# Tree.net
KiCad netlist of a schematic drawn in Altium Designer
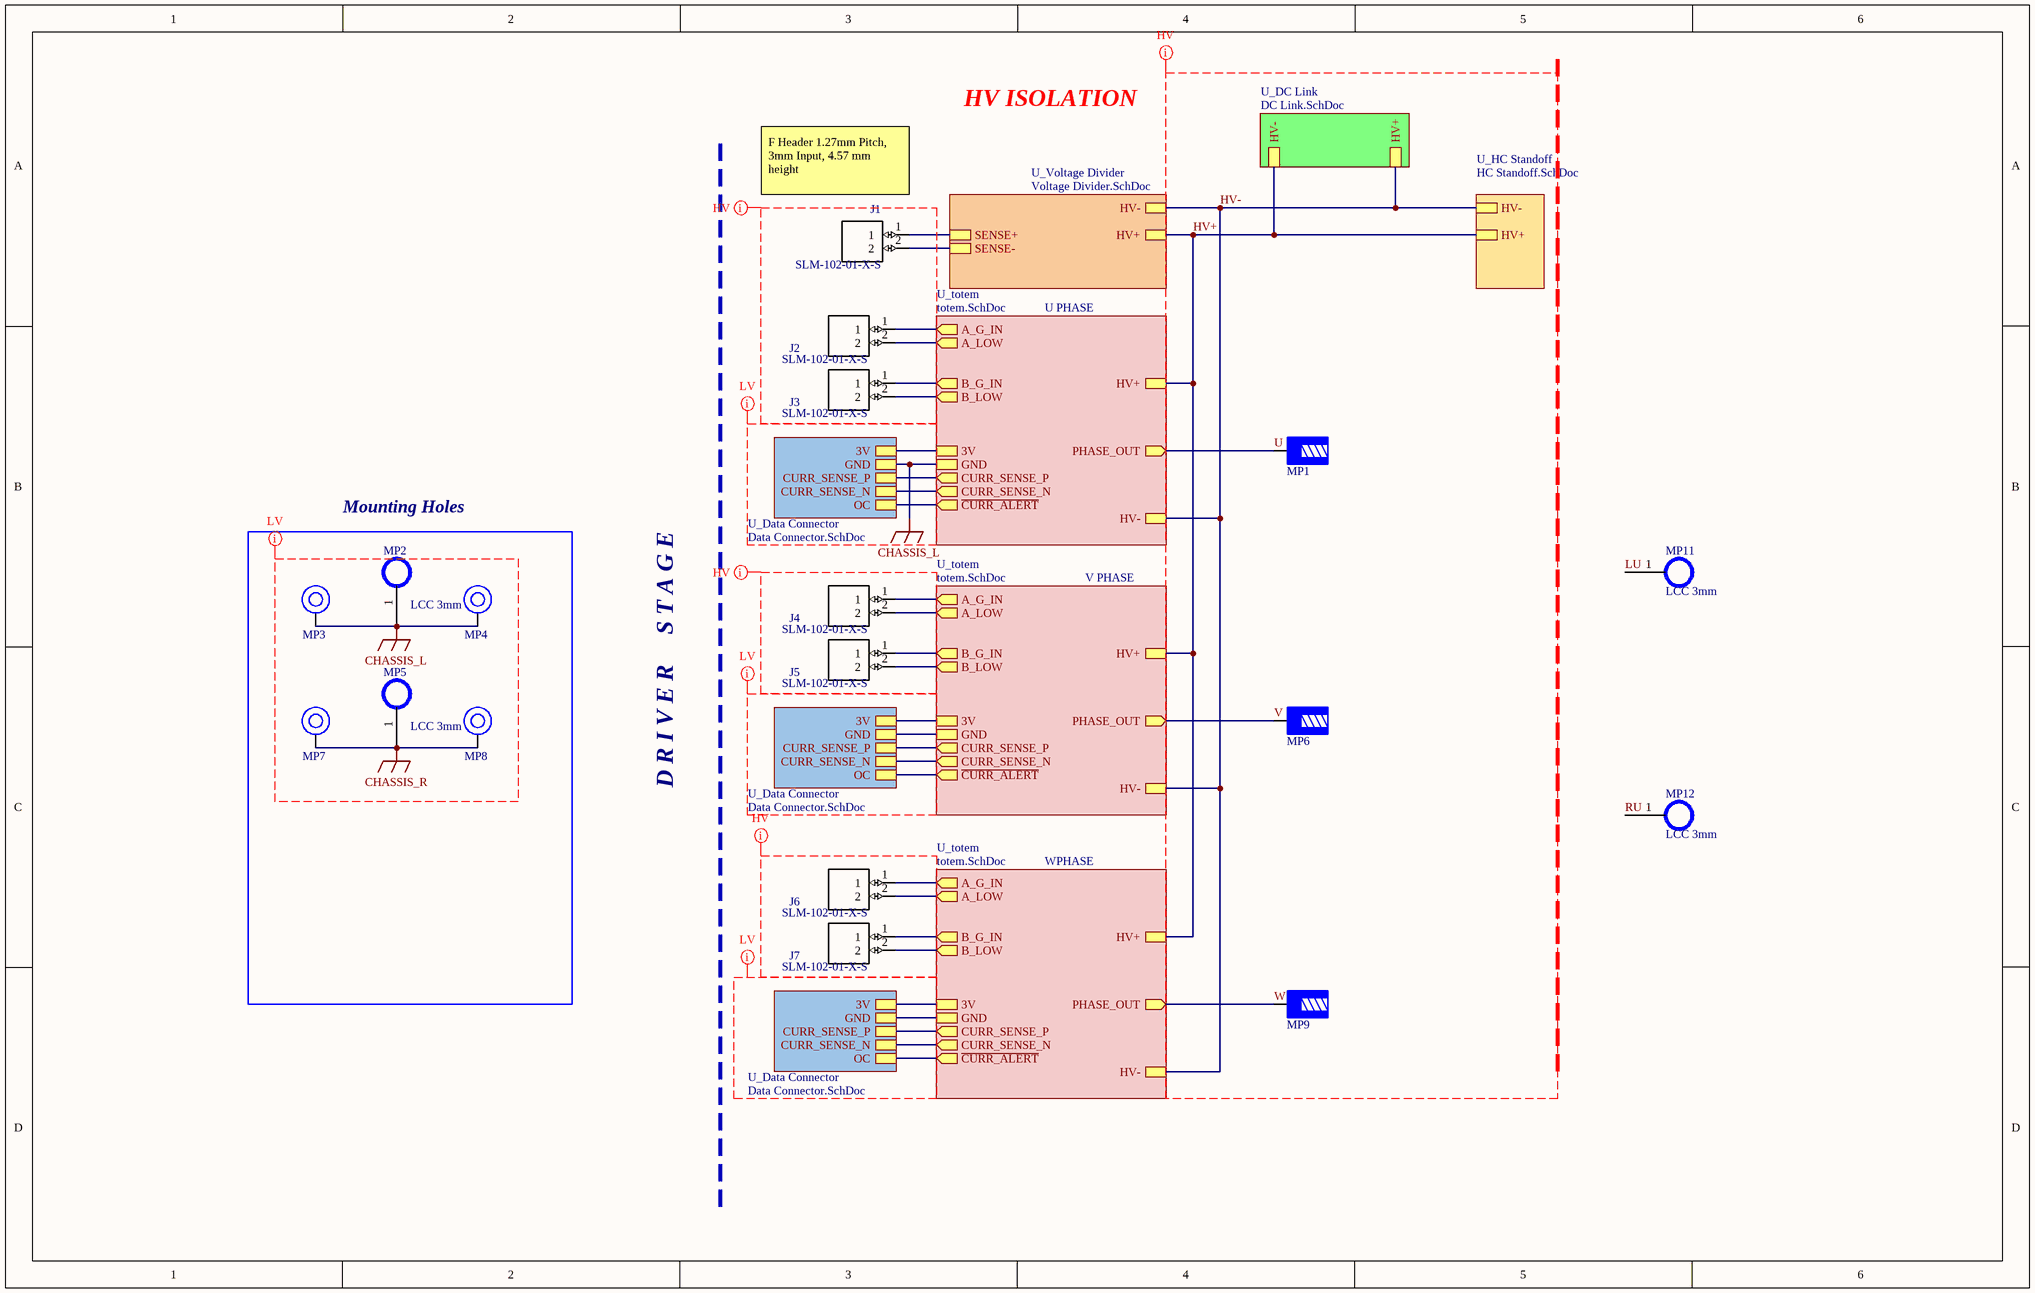
[diagram p0: Tree.SchDoc]

(export (version "E")
  (design (tool "Eeschema 10.0.6"))
  (components
    (comp (ref "J1")
      (value "SLM-102-01-X-S")
      (footprint "*SLM-102-01-X-S")
      (libsource (lib "Schlib1") (part "SLM-102-01-X-S"))
    )
    (comp (ref "J2")
      (value "SLM-102-01-X-S")
      (footprint "*SLM-102-01-X-S")
      (libsource (lib "Schlib1") (part "SLM-102-01-X-S"))
    )
    (comp (ref "J3")
      (value "SLM-102-01-X-S")
      (footprint "*SLM-102-01-X-S")
      (libsource (lib "Schlib1") (part "SLM-102-01-X-S"))
    )
    (comp (ref "J4")
      (value "SLM-102-01-X-S")
      (footprint "*SLM-102-01-X-S")
      (libsource (lib "Schlib1") (part "SLM-102-01-X-S"))
    )
    (comp (ref "J5")
      (value "SLM-102-01-X-S")
      (footprint "*SLM-102-01-X-S")
      (libsource (lib "Schlib1") (part "SLM-102-01-X-S"))
    )
    (comp (ref "J6")
      (value "SLM-102-01-X-S")
      (footprint "*SLM-102-01-X-S")
      (libsource (lib "Schlib1") (part "SLM-102-01-X-S"))
    )
    (comp (ref "J7")
      (value "SLM-102-01-X-S")
      (footprint "*SLM-102-01-X-S")
      (libsource (lib "Schlib1") (part "SLM-102-01-X-S"))
    )
    (comp (ref "MP1")
      (value "M5 x 6mm")
      (footprint "7460305_HAL")
      (description "WP-BUTR REDCUBE PRESS-FIT with internal thread, two-rows, L9W9H7mm, M5 x 6mm, 160A")
      (fields
        (field (name "MANUFACTURER PART NUMBER") "7460305")
        (field (name "MANUFACTURER") "Wurth Elektronik")
      )
      (libsource (lib "Schlib1") (part "7460305"))
    )
    (comp (ref "MP2") (value "LCC 3mm") (footprint "PAD 3MM") (libsource (lib "Schlib1") (part "LCC 3mm")))
    (comp (ref "MP3")
      (value "hole 3.3mm x 6mm")
      (footprint "9774060960")
      (description "WA-SMST SMT Steel Spacer, OD 6mm, hole 3.3mm x 6mm")
      (fields
        (field (name "MANUFACTURER PART NUMBER") "9774060960R")
        (field (name "MANUFACTURER") "Wurth Elektronik")
      )
      (libsource (lib "Schlib1") (part "9774060960R"))
    )
    (comp (ref "MP4")
      (value "hole 3.3mm x 6mm")
      (footprint "9774060960")
      (description "WA-SMST SMT Steel Spacer, OD 6mm, hole 3.3mm x 6mm")
      (fields
        (field (name "MANUFACTURER PART NUMBER") "9774060960R")
        (field (name "MANUFACTURER") "Wurth Elektronik")
      )
      (libsource (lib "Schlib1") (part "9774060960R"))
    )
    (comp (ref "MP5") (value "LCC 3mm") (footprint "PAD 3MM") (libsource (lib "Schlib1") (part "LCC 3mm")))
    (comp (ref "MP6")
      (value "M5 x 6mm")
      (footprint "7460305_HAL")
      (description "WP-BUTR REDCUBE PRESS-FIT with internal thread, two-rows, L9W9H7mm, M5 x 6mm, 160A")
      (fields
        (field (name "MANUFACTURER PART NUMBER") "7460305")
        (field (name "MANUFACTURER") "Wurth Elektronik")
      )
      (libsource (lib "Schlib1") (part "7460305"))
    )
    (comp (ref "MP7")
      (value "hole 3.3mm x 6mm")
      (footprint "9774060960")
      (description "WA-SMST SMT Steel Spacer, OD 6mm, hole 3.3mm x 6mm")
      (fields
        (field (name "MANUFACTURER PART NUMBER") "9774060960R")
        (field (name "MANUFACTURER") "Wurth Elektronik")
      )
      (libsource (lib "Schlib1") (part "9774060960R"))
    )
    (comp (ref "MP8")
      (value "hole 3.3mm x 6mm")
      (footprint "9774060960")
      (description "WA-SMST SMT Steel Spacer, OD 6mm, hole 3.3mm x 6mm")
      (fields
        (field (name "MANUFACTURER PART NUMBER") "9774060960R")
        (field (name "MANUFACTURER") "Wurth Elektronik")
      )
      (libsource (lib "Schlib1") (part "9774060960R"))
    )
    (comp (ref "MP9")
      (value "M5 x 6mm")
      (footprint "7460305_HAL")
      (description "WP-BUTR REDCUBE PRESS-FIT with internal thread, two-rows, L9W9H7mm, M5 x 6mm, 160A")
      (fields
        (field (name "MANUFACTURER PART NUMBER") "7460305")
        (field (name "MANUFACTURER") "Wurth Elektronik")
      )
      (libsource (lib "Schlib1") (part "7460305"))
    )
    (comp (ref "MP11") (value "LCC 3mm") (footprint "PAD 3MM") (libsource (lib "Schlib1") (part "LCC 3mm")))
    (comp (ref "MP12") (value "LCC 3mm") (footprint "PAD 3MM") (libsource (lib "Schlib1") (part "LCC 3mm")))
  )
  (nets
    (net (code "4") (name "/A_G_IN") (class "Default")
      (node (ref "J2") (pin "1") (pinfunction "1_1") (pintype "bidirectional"))
    )
    (net (code "5") (name "/A_G_IN_1") (class "Default")
      (node (ref "J4") (pin "1") (pinfunction "1_1") (pintype "bidirectional"))
    )
    (net (code "6") (name "/A_G_IN_2") (class "Default")
      (node (ref "J6") (pin "1") (pinfunction "1_1") (pintype "bidirectional"))
    )
    (net (code "7") (name "/A_LOW") (class "Default")
      (node (ref "J2") (pin "2") (pinfunction "2_2") (pintype "bidirectional"))
    )
    (net (code "8") (name "/A_LOW_1") (class "Default")
      (node (ref "J4") (pin "2") (pinfunction "2_2") (pintype "bidirectional"))
    )
    (net (code "9") (name "/A_LOW_2") (class "Default")
      (node (ref "J6") (pin "2") (pinfunction "2_2") (pintype "bidirectional"))
    )
    (net (code "10") (name "/B_G_IN") (class "Default")
      (node (ref "J3") (pin "1") (pinfunction "1_1") (pintype "bidirectional"))
    )
    (net (code "11") (name "/B_G_IN_1") (class "Default")
      (node (ref "J5") (pin "1") (pinfunction "1_1") (pintype "bidirectional"))
    )
    (net (code "12") (name "/B_G_IN_2") (class "Default")
      (node (ref "J7") (pin "1") (pinfunction "1_1") (pintype "bidirectional"))
    )
    (net (code "13") (name "/B_LOW") (class "Default")
      (node (ref "J3") (pin "2") (pinfunction "2_2") (pintype "bidirectional"))
    )
    (net (code "14") (name "/B_LOW_1") (class "Default")
      (node (ref "J5") (pin "2") (pinfunction "2_2") (pintype "bidirectional"))
    )
    (net (code "15") (name "/B_LOW_2") (class "Default")
      (node (ref "J7") (pin "2") (pinfunction "2_2") (pintype "bidirectional"))
    )
    (net (code "26") (name "/LU") (class "Default") (node (ref "MP11") (pin "1") (pintype "passive")))
    (net (code "27") (name "/RU") (class "Default") (node (ref "MP12") (pin "1") (pintype "passive")))
    (net (code "28") (name "/SENSE+") (class "Default")
      (node (ref "J1") (pin "1") (pinfunction "1_1") (pintype "bidirectional"))
    )
    (net (code "29") (name "/SENSE-") (class "Default")
      (node (ref "J1") (pin "2") (pinfunction "2_2") (pintype "bidirectional"))
    )
    (net (code "30") (name "/U") (class "Default")
      (node (ref "MP1") (pin "1") (pinfunction "1_1") (pintype "passive"))
    )
    (net (code "31") (name "/V") (class "Default")
      (node (ref "MP6") (pin "1") (pinfunction "1_1") (pintype "passive"))
    )
    (net (code "32") (name "/W") (class "Default")
      (node (ref "MP9") (pin "1") (pinfunction "1_1") (pintype "passive"))
    )
    (net (code "36") (name "CHASSIS_L") (class "Default")
      (node (ref "MP2") (pin "1") (pintype "passive"))
      (node (ref "MP3") (pin "1") (pinfunction "1_1") (pintype "passive"))
      (node (ref "MP4") (pin "1") (pinfunction "1_1") (pintype "passive"))
    )
    (net (code "37") (name "CHASSIS_R") (class "Default")
      (node (ref "MP5") (pin "1") (pintype "passive"))
      (node (ref "MP7") (pin "1") (pinfunction "1_1") (pintype "passive"))
      (node (ref "MP8") (pin "1") (pinfunction "1_1") (pintype "passive"))
    )
  )
)
